# 3__I2C_TO_UART.net
KiCad netlist of a schematic drawn in Altium Designer
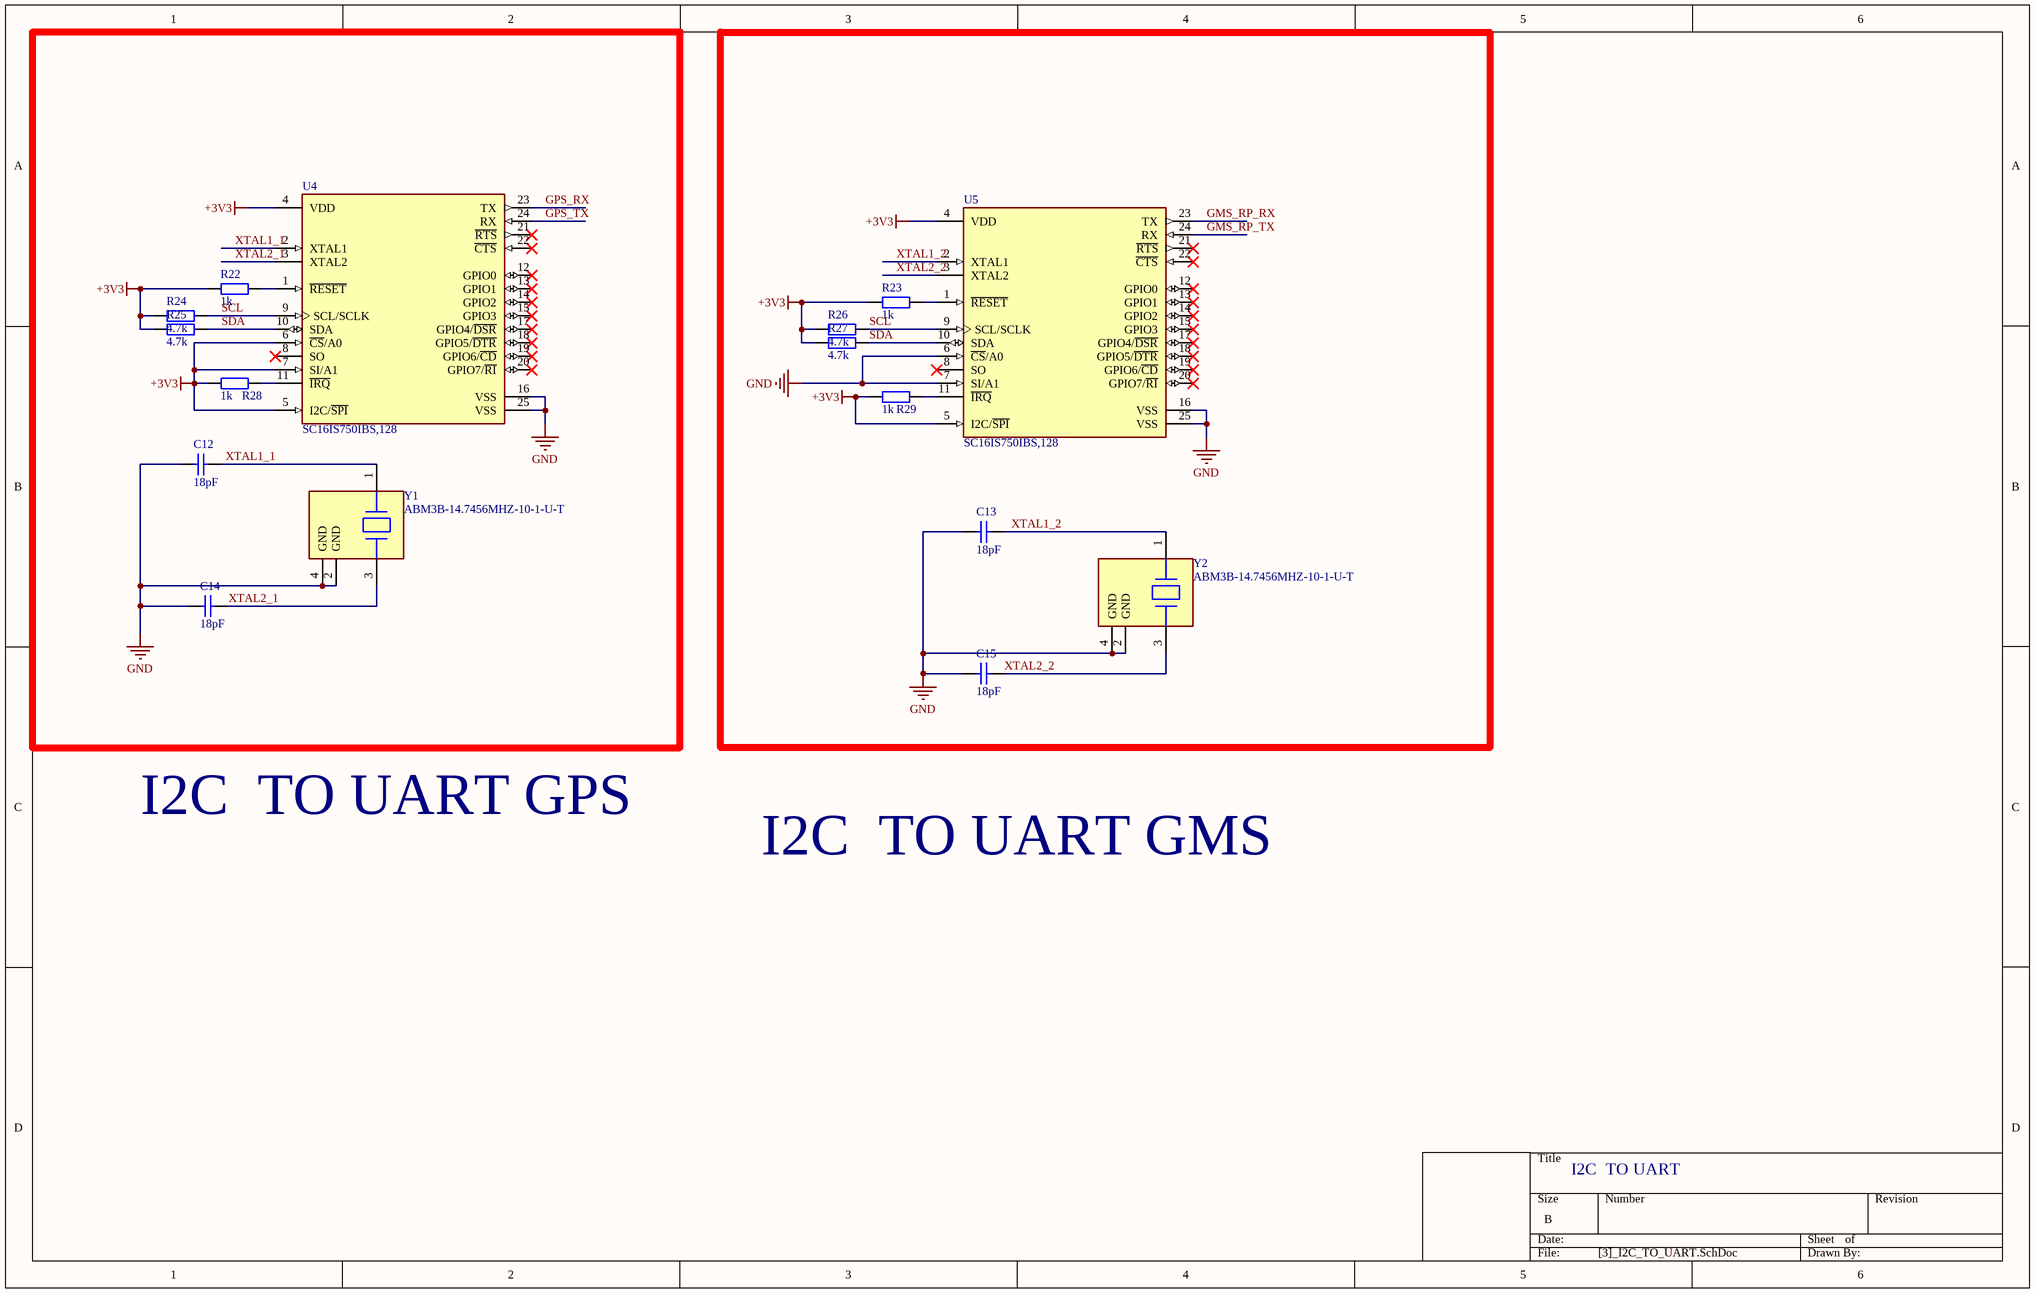
[diagram p0: [3]_I2C_TO_UART.SchDoc]

(export (version "E")
  (design (tool "Eeschema 10.0.6"))
  (components
    (comp (ref "C12")
      (value "18pF")
      (footprint "tu 0603")
      (description "Dán")
      (libsource (lib "Altium_Lib_by_KhueNguyenCreator") (part "Tu 0603 22pF 50V 10%"))
    )
    (comp (ref "C13")
      (value "18pF")
      (footprint "tu 0603")
      (description "Dán")
      (libsource (lib "Altium_Lib_by_KhueNguyenCreator") (part "Tu 0603 22pF 50V 10%"))
    )
    (comp (ref "C14")
      (value "18pF")
      (footprint "tu 0603")
      (description "Dán")
      (libsource (lib "Altium_Lib_by_KhueNguyenCreator") (part "Tu 0603 22pF 50V 10%"))
    )
    (comp (ref "C15")
      (value "18pF")
      (footprint "tu 0603")
      (description "Dán")
      (libsource (lib "Altium_Lib_by_KhueNguyenCreator") (part "Tu 0603 22pF 50V 10%"))
    )
    (comp (ref "R22")
      (value "1k")
      (footprint "tro smd 0603")
      (description "Dán")
      (libsource (lib "Altium_Lib_by_KhueNguyenCreator") (part "Tro 0603 1% 1k"))
    )
    (comp (ref "R23")
      (value "1k")
      (footprint "tro smd 0603")
      (description "Dán")
      (libsource (lib "Altium_Lib_by_KhueNguyenCreator") (part "Tro 0603 1% 1k"))
    )
    (comp (ref "R24")
      (value "4.7k")
      (footprint "tro smd 0603")
      (description "Dán")
      (libsource (lib "Altium_Lib_by_KhueNguyenCreator") (part "Tro 0603 1% 1k"))
    )
    (comp (ref "R25")
      (value "4.7k")
      (footprint "tro smd 0603")
      (description "Dán")
      (libsource (lib "Altium_Lib_by_KhueNguyenCreator") (part "Tro 0603 1% 1k"))
    )
    (comp (ref "R26")
      (value "4.7k")
      (footprint "tro smd 0603")
      (description "Dán")
      (libsource (lib "Altium_Lib_by_KhueNguyenCreator") (part "Tro 0603 1% 1k"))
    )
    (comp (ref "R27")
      (value "4.7k")
      (footprint "tro smd 0603")
      (description "Dán")
      (libsource (lib "Altium_Lib_by_KhueNguyenCreator") (part "Tro 0603 1% 1k"))
    )
    (comp (ref "R28")
      (value "1k")
      (footprint "tro smd 0603")
      (description "Dán")
      (libsource (lib "Altium_Lib_by_KhueNguyenCreator") (part "Tro 0603 1% 1k"))
    )
    (comp (ref "R29")
      (value "1k")
      (footprint "tro smd 0603")
      (description "Dán")
      (libsource (lib "Altium_Lib_by_KhueNguyenCreator") (part "Tro 0603 1% 1k"))
    )
    (comp (ref "U4")
      (value "SC16IS750IBS,128")
      (footprint "FP-SOT616-3-MFG")
      (description "IC UART I2C/SPI 24-HVQFN")
      (libsource (lib "Altium Content Vault") (part "79c44373c93ef5f8960d91c990d60c9"))
    )
    (comp (ref "U5")
      (value "SC16IS750IBS,128")
      (footprint "FP-SOT616-3-MFG")
      (description "IC UART I2C/SPI 24-HVQFN")
      (libsource (lib "Altium Content Vault") (part "79c44373c93ef5f8960d91c990d60c9"))
    )
    (comp (ref "Y1")
      (value "ABM3B-14.7456MHZ-10-1-U-T")
      (footprint "FP-ABM3B-MFG")
      (description "Crystal 14.7456MHz ±10ppm 10pF SMD-4 5mm x 3.2mm")
      (fields (field (name "TOLERANCE") "10ppm"))
      (libsource (lib "Altium Content Vault") (part "48e526d86b7f2615d98721063c72f49"))
    )
    (comp (ref "Y2")
      (value "ABM3B-14.7456MHZ-10-1-U-T")
      (footprint "FP-ABM3B-MFG")
      (description "Crystal 14.7456MHz ±10ppm 10pF SMD-4 5mm x 3.2mm")
      (fields (field (name "TOLERANCE") "10ppm"))
      (libsource (lib "Altium Content Vault") (part "48e526d86b7f2615d98721063c72f49"))
    )
  )
  (nets
    (net (code "1") (name "+3V3") (class "Default")
      (node (ref "R22") (pin "1") (pinfunction "1_1") (pintype "passive"))
      (node (ref "R23") (pin "1") (pinfunction "1_1") (pintype "passive"))
      (node (ref "R24") (pin "1") (pinfunction "1_1") (pintype "passive"))
      (node (ref "R25") (pin "1") (pinfunction "1_1") (pintype "passive"))
      (node (ref "R26") (pin "1") (pinfunction "1_1") (pintype "passive"))
      (node (ref "R27") (pin "1") (pinfunction "1_1") (pintype "passive"))
      (node (ref "R28") (pin "1") (pinfunction "1_1") (pintype "passive"))
      (node (ref "R29") (pin "1") (pinfunction "1_1") (pintype "passive"))
      (node (ref "U4") (pin "4") (pinfunction "VDD_4") (pintype "power_in"))
      (node (ref "U4") (pin "5") (pinfunction "I2C/~{SPI}_5") (pintype "input"))
      (node (ref "U4") (pin "6") (pinfunction "~{CS}/A0_6") (pintype "input"))
      (node (ref "U4") (pin "7") (pinfunction "SI/A1_7") (pintype "input"))
      (node (ref "U5") (pin "4") (pinfunction "VDD_4") (pintype "power_in"))
      (node (ref "U5") (pin "5") (pinfunction "I2C/~{SPI}_5") (pintype "input"))
    )
    (net (code "2") (name "/GMS_RP_RX") (class "Default")
      (node (ref "U5") (pin "23") (pinfunction "TX_23") (pintype "output"))
    )
    (net (code "3") (name "/GMS_RP_TX") (class "Default")
      (node (ref "U5") (pin "24") (pinfunction "RX_24") (pintype "input"))
    )
    (net (code "4") (name "/GPS_RX") (class "Default")
      (node (ref "U4") (pin "23") (pinfunction "TX_23") (pintype "output"))
    )
    (net (code "5") (name "/GPS_TX") (class "Default")
      (node (ref "U4") (pin "24") (pinfunction "RX_24") (pintype "input"))
    )
    (net (code "6") (name "/SCL") (class "Default")
      (node (ref "R24") (pin "2") (pinfunction "2_2") (pintype "passive"))
      (node (ref "R26") (pin "2") (pinfunction "2_2") (pintype "passive"))
      (node (ref "U4") (pin "9") (pinfunction "SCL/SCLK_9") (pintype "input"))
      (node (ref "U5") (pin "9") (pinfunction "SCL/SCLK_9") (pintype "input"))
    )
    (net (code "7") (name "/SDA") (class "Default")
      (node (ref "R25") (pin "2") (pinfunction "2_2") (pintype "passive"))
      (node (ref "R27") (pin "2") (pinfunction "2_2") (pintype "passive"))
      (node (ref "U4") (pin "10") (pinfunction "SDA_10") (pintype "bidirectional"))
      (node (ref "U5") (pin "10") (pinfunction "SDA_10") (pintype "bidirectional"))
    )
    (net (code "8") (name "/XTAL1_1") (class "Default")
      (node (ref "C12") (pin "1") (pinfunction "1_1") (pintype "passive"))
      (node (ref "U4") (pin "2") (pinfunction "XTAL1_2") (pintype "input"))
      (node (ref "Y1") (pin "1") (pinfunction "1_1") (pintype "passive"))
    )
    (net (code "9") (name "/XTAL1_2") (class "Default")
      (node (ref "C13") (pin "1") (pinfunction "1_1") (pintype "passive"))
      (node (ref "U5") (pin "2") (pinfunction "XTAL1_2") (pintype "input"))
      (node (ref "Y2") (pin "1") (pinfunction "1_1") (pintype "passive"))
    )
    (net (code "10") (name "/XTAL2_1") (class "Default")
      (node (ref "C14") (pin "1") (pinfunction "1_1") (pintype "passive"))
      (node (ref "U4") (pin "3") (pinfunction "XTAL2_3") (pintype "passive"))
      (node (ref "Y1") (pin "3") (pinfunction "3_3") (pintype "passive"))
    )
    (net (code "11") (name "/XTAL2_2") (class "Default")
      (node (ref "C15") (pin "1") (pinfunction "1_1") (pintype "passive"))
      (node (ref "U5") (pin "3") (pinfunction "XTAL2_3") (pintype "passive"))
      (node (ref "Y2") (pin "3") (pinfunction "3_3") (pintype "passive"))
    )
    (net (code "12") (name "GND") (class "Default")
      (node (ref "C12") (pin "2") (pinfunction "2_2") (pintype "passive"))
      (node (ref "C13") (pin "2") (pinfunction "2_2") (pintype "passive"))
      (node (ref "C14") (pin "2") (pinfunction "2_2") (pintype "passive"))
      (node (ref "C15") (pin "2") (pinfunction "2_2") (pintype "passive"))
      (node (ref "U4") (pin "16") (pinfunction "VSS_16") (pintype "power_in"))
      (node (ref "U4") (pin "25") (pinfunction "VSS_25") (pintype "power_in"))
      (node (ref "U5") (pin "16") (pinfunction "VSS_16") (pintype "power_in"))
      (node (ref "U5") (pin "25") (pinfunction "VSS_25") (pintype "power_in"))
      (node (ref "U5") (pin "6") (pinfunction "~{CS}/A0_6") (pintype "input"))
      (node (ref "U5") (pin "7") (pinfunction "SI/A1_7") (pintype "input"))
      (node (ref "Y1") (pin "2") (pinfunction "GND_2") (pintype "power_in"))
      (node (ref "Y1") (pin "4") (pinfunction "GND_4") (pintype "power_in"))
      (node (ref "Y2") (pin "2") (pinfunction "GND_2") (pintype "power_in"))
      (node (ref "Y2") (pin "4") (pinfunction "GND_4") (pintype "power_in"))
    )
    (net (code "13") (name "Net-(U4-~{IRQ})") (class "Default")
      (node (ref "R28") (pin "2") (pinfunction "2_2") (pintype "passive"))
      (node (ref "U4") (pin "11") (pinfunction "~{IRQ}_11") (pintype "open_collector"))
    )
    (net (code "14") (name "Net-(U4-~{RESET})") (class "Default")
      (node (ref "R22") (pin "2") (pinfunction "2_2") (pintype "passive"))
      (node (ref "U4") (pin "1") (pinfunction "~{RESET}_1") (pintype "input"))
    )
    (net (code "15") (name "Net-(U5-~{IRQ})") (class "Default")
      (node (ref "R29") (pin "2") (pinfunction "2_2") (pintype "passive"))
      (node (ref "U5") (pin "11") (pinfunction "~{IRQ}_11") (pintype "open_collector"))
    )
    (net (code "16") (name "Net-(U5-~{RESET})") (class "Default")
      (node (ref "R23") (pin "2") (pinfunction "2_2") (pintype "passive"))
      (node (ref "U5") (pin "1") (pinfunction "~{RESET}_1") (pintype "input"))
    )
    (net (code "17") (name "unconnected-(U4-GPIO0-Pad12)") (class "Default")
      (node (ref "U4") (pin "12") (pinfunction "GPIO0_12") (pintype "bidirectional+no_connect"))
    )
    (net (code "18") (name "unconnected-(U4-GPIO1-Pad13)") (class "Default")
      (node (ref "U4") (pin "13") (pinfunction "GPIO1_13") (pintype "bidirectional+no_connect"))
    )
    (net (code "19") (name "unconnected-(U4-GPIO2-Pad14)") (class "Default")
      (node (ref "U4") (pin "14") (pinfunction "GPIO2_14") (pintype "bidirectional+no_connect"))
    )
    (net (code "20") (name "unconnected-(U4-GPIO3-Pad15)") (class "Default")
      (node (ref "U4") (pin "15") (pinfunction "GPIO3_15") (pintype "bidirectional+no_connect"))
    )
    (net (code "21") (name "unconnected-(U4-GPIO4{slash}~{DSR}-Pad17)") (class "Default")
      (node (ref "U4") (pin "17") (pinfunction "GPIO4/~{DSR}_17") (pintype "bidirectional+no_connect"))
    )
    (net (code "22") (name "unconnected-(U4-GPIO5{slash}~{DTR}-Pad18)") (class "Default")
      (node (ref "U4") (pin "18") (pinfunction "GPIO5/~{DTR}_18") (pintype "bidirectional+no_connect"))
    )
    (net (code "23") (name "unconnected-(U4-GPIO6{slash}~{CD}-Pad19)") (class "Default")
      (node (ref "U4") (pin "19") (pinfunction "GPIO6/~{CD}_19") (pintype "bidirectional+no_connect"))
    )
    (net (code "24") (name "unconnected-(U4-GPIO7{slash}~{RI}-Pad20)") (class "Default")
      (node (ref "U4") (pin "20") (pinfunction "GPIO7/~{RI}_20") (pintype "bidirectional+no_connect"))
    )
    (net (code "25") (name "unconnected-(U4-SO-Pad8)") (class "Default")
      (node (ref "U4") (pin "8") (pinfunction "SO_8") (pintype "passive+no_connect"))
    )
    (net (code "26") (name "unconnected-(U4-~{CTS}-Pad22)") (class "Default")
      (node (ref "U4") (pin "22") (pinfunction "~{CTS}_22") (pintype "input+no_connect"))
    )
    (net (code "27") (name "unconnected-(U4-~{RTS}-Pad21)") (class "Default")
      (node (ref "U4") (pin "21") (pinfunction "~{RTS}_21") (pintype "output+no_connect"))
    )
    (net (code "28") (name "unconnected-(U5-GPIO0-Pad12)") (class "Default")
      (node (ref "U5") (pin "12") (pinfunction "GPIO0_12") (pintype "bidirectional+no_connect"))
    )
    (net (code "29") (name "unconnected-(U5-GPIO1-Pad13)") (class "Default")
      (node (ref "U5") (pin "13") (pinfunction "GPIO1_13") (pintype "bidirectional+no_connect"))
    )
    (net (code "30") (name "unconnected-(U5-GPIO2-Pad14)") (class "Default")
      (node (ref "U5") (pin "14") (pinfunction "GPIO2_14") (pintype "bidirectional+no_connect"))
    )
    (net (code "31") (name "unconnected-(U5-GPIO3-Pad15)") (class "Default")
      (node (ref "U5") (pin "15") (pinfunction "GPIO3_15") (pintype "bidirectional+no_connect"))
    )
    (net (code "32") (name "unconnected-(U5-GPIO4{slash}~{DSR}-Pad17)") (class "Default")
      (node (ref "U5") (pin "17") (pinfunction "GPIO4/~{DSR}_17") (pintype "bidirectional+no_connect"))
    )
    (net (code "33") (name "unconnected-(U5-GPIO5{slash}~{DTR}-Pad18)") (class "Default")
      (node (ref "U5") (pin "18") (pinfunction "GPIO5/~{DTR}_18") (pintype "bidirectional+no_connect"))
    )
    (net (code "34") (name "unconnected-(U5-GPIO6{slash}~{CD}-Pad19)") (class "Default")
      (node (ref "U5") (pin "19") (pinfunction "GPIO6/~{CD}_19") (pintype "bidirectional+no_connect"))
    )
    (net (code "35") (name "unconnected-(U5-GPIO7{slash}~{RI}-Pad20)") (class "Default")
      (node (ref "U5") (pin "20") (pinfunction "GPIO7/~{RI}_20") (pintype "bidirectional+no_connect"))
    )
    (net (code "36") (name "unconnected-(U5-SO-Pad8)") (class "Default")
      (node (ref "U5") (pin "8") (pinfunction "SO_8") (pintype "passive+no_connect"))
    )
    (net (code "37") (name "unconnected-(U5-~{CTS}-Pad22)") (class "Default")
      (node (ref "U5") (pin "22") (pinfunction "~{CTS}_22") (pintype "input+no_connect"))
    )
    (net (code "38") (name "unconnected-(U5-~{RTS}-Pad21)") (class "Default")
      (node (ref "U5") (pin "21") (pinfunction "~{RTS}_21") (pintype "output+no_connect"))
    )
  )
)
